# CAN-USB_adapter.net
KiCad netlist of a schematic drawn in EAGLE
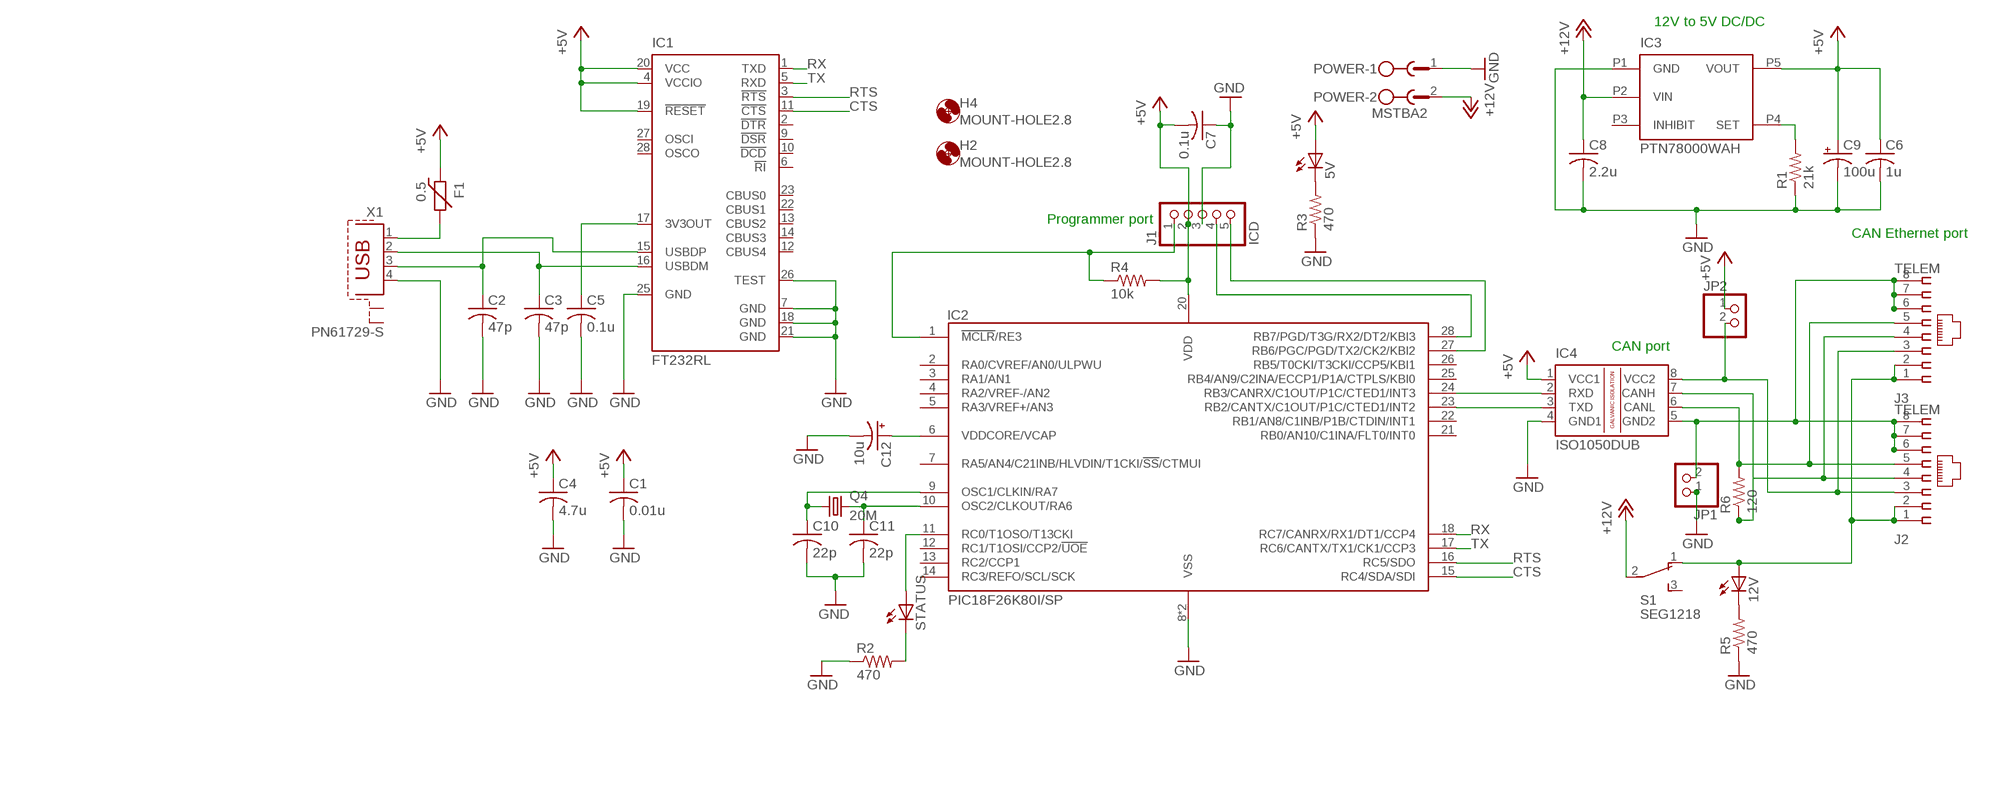
[diagram p0: schematic, sheet 1]

(export (version "E")
  (design (tool "Eeschema 10.0.6"))
  (components
    (comp (ref "5V")
      (value "LED5MM")
      (footprint "eagle-import:LED5MM")
      (libsource (lib "eagle-import") (part "LED5MM"))
    )
    (comp (ref "12V")
      (value "LED5MM")
      (footprint "eagle-import:LED5MM")
      (libsource (lib "eagle-import") (part "LED5MM"))
    )
    (comp (ref "C1")
      (value "0.01u")
      (footprint "eagle-import:C0805")
      (libsource (lib "eagle-import") (part "resistor_C-USC0805"))
    )
    (comp (ref "C2")
      (value "47p")
      (footprint "eagle-import:C0805")
      (libsource (lib "eagle-import") (part "resistor_C-USC0805"))
    )
    (comp (ref "C3")
      (value "47p")
      (footprint "eagle-import:C0805")
      (libsource (lib "eagle-import") (part "resistor_C-USC0805"))
    )
    (comp (ref "C4")
      (value "4.7u")
      (footprint "eagle-import:C0805")
      (libsource (lib "eagle-import") (part "resistor_C-USC0805"))
    )
    (comp (ref "C5")
      (value "0.1u")
      (footprint "eagle-import:C0805")
      (libsource (lib "eagle-import") (part "resistor_C-USC0805"))
    )
    (comp (ref "C6")
      (value "1u")
      (footprint "eagle-import:C0805")
      (libsource (lib "eagle-import") (part "C-USC0805"))
    )
    (comp (ref "C7")
      (value "0.1u")
      (footprint "eagle-import:C0805")
      (libsource (lib "eagle-import") (part "C-USC0805"))
    )
    (comp (ref "C8")
      (value "2.2u")
      (footprint "eagle-import:C1206")
      (libsource (lib "eagle-import") (part "C-USC1206"))
    )
    (comp (ref "C9")
      (value "100u")
      (footprint "eagle-import:SMC_D")
      (libsource (lib "eagle-import") (part "CPOL-USSMCD"))
    )
    (comp (ref "C10")
      (value "22p")
      (footprint "eagle-import:C0805")
      (libsource (lib "eagle-import") (part "C-USC0805"))
    )
    (comp (ref "C11")
      (value "22p")
      (footprint "eagle-import:C0805")
      (libsource (lib "eagle-import") (part "C-USC0805"))
    )
    (comp (ref "C12")
      (value "10u")
      (footprint "eagle-import:TT2D4")
      (libsource (lib "eagle-import") (part "CPOL-USTT2D4"))
    )
    (comp (ref "F1")
      (value "0.5")
      (footprint "eagle-import:F1206")
      (libsource (lib "eagle-import") (part "PTC0ZCA"))
    )
    (comp (ref "H2")
      (value "MOUNT-HOLE2.8")
      (footprint "eagle-import:2,8")
      (libsource (lib "eagle-import") (part "MOUNT-HOLE2.8"))
    )
    (comp (ref "H4")
      (value "MOUNT-HOLE2.8")
      (footprint "eagle-import:2,8")
      (libsource (lib "eagle-import") (part "MOUNT-HOLE2.8"))
    )
    (comp (ref "IC1")
      (value "FT232RL")
      (footprint "eagle-import:SSOP28")
      (libsource (lib "eagle-import") (part "FT232RL"))
    )
    (comp (ref "IC2")
      (value "PIC18F26K80I/SP")
      (footprint "eagle-import:DIL28_3")
      (libsource (lib "eagle-import") (part "PIC18F26K80I/SP"))
    )
    (comp (ref "IC3")
      (value "PTN78000WAH")
      (footprint "eagle-import:PTN78000")
      (libsource (lib "eagle-import") (part "PTN78000WAH"))
    )
    (comp (ref "IC4")
      (value "ISO1050DUB")
      (footprint "eagle-import:DUB-R-PDSO-G8")
      (fields (field (name "MPN") "ISO1050DUBR"))
      (libsource (lib "eagle-import") (part "ISO1050DUB"))
    )
    (comp (ref "J1")
      (value "ICD")
      (footprint "eagle-import:1X05")
      (libsource (lib "eagle-import") (part "PINHD-1X5"))
    )
    (comp (ref "J2")
      (value "TELEM")
      (footprint "eagle-import:215877-7")
      (libsource (lib "eagle-import") (part "215877-7"))
    )
    (comp (ref "J3")
      (value "TELEM")
      (footprint "eagle-import:215877-7")
      (libsource (lib "eagle-import") (part "215877-7"))
    )
    (comp (ref "JP1")
      (value "PINHD-1X2")
      (footprint "eagle-import:1X02")
      (libsource (lib "eagle-import") (part "PINHD-1X2"))
    )
    (comp (ref "JP2")
      (value "PINHD-1X2")
      (footprint "eagle-import:1X02")
      (libsource (lib "eagle-import") (part "PINHD-1X2"))
    )
    (comp (ref "POWER")
      (value "MSTBA2")
      (footprint "eagle-import:MSTBA2")
      (fields (field (name "MF") "FARNELL") (field (name "MPN") "1757242"))
      (libsource (lib "eagle-import") (part "MSTBA2"))
    )
    (comp (ref "Q4")
      (value "20M")
      (footprint "eagle-import:HC49_S")
      (libsource (lib "eagle-import") (part "CRYSTALHC49S"))
    )
    (comp (ref "R1")
      (value "21k")
      (footprint "eagle-import:R0805")
      (libsource (lib "eagle-import") (part "rcl_R-US_R0805"))
    )
    (comp (ref "R2")
      (value "470")
      (footprint "eagle-import:R0805")
      (libsource (lib "eagle-import") (part "rcl_R-US_R0805"))
    )
    (comp (ref "R3")
      (value "470")
      (footprint "eagle-import:R0805")
      (libsource (lib "eagle-import") (part "rcl_R-US_R0805"))
    )
    (comp (ref "R4")
      (value "10k")
      (footprint "eagle-import:R0805")
      (libsource (lib "eagle-import") (part "rcl_R-US_R0805"))
    )
    (comp (ref "R5")
      (value "470")
      (footprint "eagle-import:R0805")
      (libsource (lib "eagle-import") (part "rcl_R-US_R0805"))
    )
    (comp (ref "R6")
      (value "120")
      (footprint "eagle-import:0207_7")
      (libsource (lib "eagle-import") (part "R-US_0207/7"))
    )
    (comp (ref "S1")
      (value "SEG1218")
      (footprint "eagle-import:EG1218")
      (libsource (lib "eagle-import") (part "SEG1218"))
    )
    (comp (ref "STATUS")
      (value "LED5MM")
      (footprint "eagle-import:LED5MM")
      (libsource (lib "eagle-import") (part "LED5MM"))
    )
    (comp (ref "X1")
      (value "PN61729-S")
      (footprint "eagle-import:PN61729-S")
      (libsource (lib "eagle-import") (part "PN61729-S"))
    )
  )
  (nets
    (net (code "1") (name "+5V") (class "Default")
      (node (ref "5V") (pin "A") (pinfunction "A_A") (pintype "passive"))
      (node (ref "C1") (pin "1") (pinfunction "1_1") (pintype "passive"))
      (node (ref "C4") (pin "1") (pinfunction "1_1") (pintype "passive"))
      (node (ref "C6") (pin "1") (pinfunction "1_1") (pintype "passive"))
      (node (ref "C7") (pin "2") (pinfunction "2_2") (pintype "passive"))
      (node (ref "C9") (pin "+") (pinfunction "+_+") (pintype "passive"))
      (node (ref "F1") (pin "1") (pinfunction "1_1") (pintype "passive"))
      (node (ref "IC1") (pin "19") (pinfunction "~{RESET}_19") (pintype "input"))
      (node (ref "IC1") (pin "20") (pinfunction "VCC_20") (pintype "power_in"))
      (node (ref "IC1") (pin "4") (pinfunction "VCCIO_4") (pintype "power_in"))
      (node (ref "IC2") (pin "20") (pinfunction "VDD_20") (pintype "power_in"))
      (node (ref "IC3") (pin "P5") (pinfunction "VOUT_P5") (pintype "power_in"))
      (node (ref "IC4") (pin "1") (pinfunction "VCC1_1") (pintype "input"))
      (node (ref "J1") (pin "2") (pinfunction "2_2") (pintype "passive"))
      (node (ref "JP2") (pin "1") (pinfunction "1_1") (pintype "passive"))
      (node (ref "R4") (pin "2") (pinfunction "2_2") (pintype "passive"))
    )
    (net (code "2") (name "+12V") (class "Default")
      (node (ref "C8") (pin "1") (pinfunction "1_1") (pintype "passive"))
      (node (ref "IC3") (pin "P2") (pinfunction "VIN_P2") (pintype "power_in"))
      (node (ref "POWER") (pin "2") (pinfunction "1_2") (pintype "passive"))
      (node (ref "S1") (pin "2") (pinfunction "P_2") (pintype "passive"))
    )
    (net (code "3") (name "/CTS") (class "Default")
      (node (ref "IC1") (pin "11") (pinfunction "~{CTS}_11") (pintype "bidirectional"))
      (node (ref "IC2") (pin "15") (pinfunction "RC4/SDA/SDI_15") (pintype "bidirectional"))
    )
    (net (code "4") (name "/RTS") (class "Default")
      (node (ref "IC1") (pin "3") (pinfunction "~{RTS}_3") (pintype "bidirectional"))
      (node (ref "IC2") (pin "16") (pinfunction "RC5/SDO_16") (pintype "bidirectional"))
    )
    (net (code "5") (name "/RX") (class "Default")
      (node (ref "IC1") (pin "1") (pinfunction "TXD_1") (pintype "output"))
      (node (ref "IC2") (pin "18") (pinfunction "RC7/CANRX/RX1/DT1/CCP4_18") (pintype "bidirectional"))
    )
    (net (code "6") (name "/TX") (class "Default")
      (node (ref "IC1") (pin "5") (pinfunction "RXD_5") (pintype "input"))
      (node (ref "IC2") (pin "17") (pinfunction "RC6/CANTX/TX1/CK1/CCP3_17") (pintype "bidirectional"))
    )
    (net (code "7") (name "GND") (class "Default")
      (node (ref "C1") (pin "2") (pinfunction "2_2") (pintype "passive"))
      (node (ref "C10") (pin "2") (pinfunction "2_2") (pintype "passive"))
      (node (ref "C11") (pin "2") (pinfunction "2_2") (pintype "passive"))
      (node (ref "C12") (pin "-") (pinfunction "-_-") (pintype "passive"))
      (node (ref "C2") (pin "2") (pinfunction "2_2") (pintype "passive"))
      (node (ref "C3") (pin "2") (pinfunction "2_2") (pintype "passive"))
      (node (ref "C4") (pin "2") (pinfunction "2_2") (pintype "passive"))
      (node (ref "C5") (pin "2") (pinfunction "2_2") (pintype "passive"))
      (node (ref "C6") (pin "2") (pinfunction "2_2") (pintype "passive"))
      (node (ref "C7") (pin "1") (pinfunction "1_1") (pintype "passive"))
      (node (ref "C8") (pin "2") (pinfunction "2_2") (pintype "passive"))
      (node (ref "C9") (pin "-") (pinfunction "-_-") (pintype "passive"))
      (node (ref "IC1") (pin "18") (pinfunction "GND_18") (pintype "power_in"))
      (node (ref "IC1") (pin "21") (pinfunction "GND_21") (pintype "power_in"))
      (node (ref "IC1") (pin "25") (pinfunction "GND_25") (pintype "power_in"))
      (node (ref "IC1") (pin "26") (pinfunction "TEST_26") (pintype "input"))
      (node (ref "IC1") (pin "7") (pinfunction "GND_7") (pintype "power_in"))
      (node (ref "IC2") (pin "19") (pinfunction "VSS_19") (pintype "power_in"))
      (node (ref "IC2") (pin "8") (pinfunction "VSS_8") (pintype "power_in"))
      (node (ref "IC3") (pin "P1") (pinfunction "GND_P1") (pintype "power_in"))
      (node (ref "IC4") (pin "4") (pinfunction "GND1_4") (pintype "input"))
      (node (ref "J1") (pin "3") (pinfunction "3_3") (pintype "passive"))
      (node (ref "JP1") (pin "1") (pinfunction "1_1") (pintype "passive"))
      (node (ref "POWER") (pin "1") (pinfunction "1_1") (pintype "passive"))
      (node (ref "R1") (pin "1") (pinfunction "1_1") (pintype "passive"))
      (node (ref "R2") (pin "1") (pinfunction "1_1") (pintype "passive"))
      (node (ref "R3") (pin "1") (pinfunction "1_1") (pintype "passive"))
      (node (ref "R5") (pin "1") (pinfunction "1_1") (pintype "passive"))
      (node (ref "X1") (pin "4") (pinfunction "4_4") (pintype "passive"))
    )
    (net (code "8") (name "Net-(5V-C)") (class "Default")
      (node (ref "5V") (pin "K") (pinfunction "C_K") (pintype "passive"))
      (node (ref "R3") (pin "2") (pinfunction "2_2") (pintype "passive"))
    )
    (net (code "9") (name "Net-(12V-C)") (class "Default")
      (node (ref "12V") (pin "K") (pinfunction "C_K") (pintype "passive"))
      (node (ref "R5") (pin "2") (pinfunction "2_2") (pintype "passive"))
    )
    (net (code "10") (name "Net-(F1-Pad2)") (class "Default")
      (node (ref "F1") (pin "2") (pinfunction "2_2") (pintype "passive"))
      (node (ref "X1") (pin "1") (pinfunction "1_1") (pintype "passive"))
    )
    (net (code "11") (name "Net-(IC1-3V3OUT)") (class "Default")
      (node (ref "C5") (pin "1") (pinfunction "1_1") (pintype "passive"))
      (node (ref "IC1") (pin "17") (pinfunction "3V3OUT_17") (pintype "output"))
    )
    (net (code "12") (name "Net-(IC1-USBDM)") (class "Default")
      (node (ref "C3") (pin "1") (pinfunction "1_1") (pintype "passive"))
      (node (ref "IC1") (pin "16") (pinfunction "USBDM_16") (pintype "bidirectional"))
      (node (ref "X1") (pin "2") (pinfunction "2_2") (pintype "passive"))
    )
    (net (code "13") (name "Net-(IC1-USBDP)") (class "Default")
      (node (ref "C2") (pin "1") (pinfunction "1_1") (pintype "passive"))
      (node (ref "IC1") (pin "15") (pinfunction "USBDP_15") (pintype "bidirectional"))
      (node (ref "X1") (pin "3") (pinfunction "3_3") (pintype "passive"))
    )
    (net (code "14") (name "Net-(IC2-OSC1{slash}CLKIN{slash}RA7)") (class "Default")
      (node (ref "C10") (pin "1") (pinfunction "1_1") (pintype "passive"))
      (node (ref "IC2") (pin "9") (pinfunction "OSC1/CLKIN/RA7_9") (pintype "bidirectional"))
      (node (ref "Q4") (pin "1") (pinfunction "1_1") (pintype "passive"))
    )
    (net (code "15") (name "Net-(IC2-OSC2{slash}CLKOUT{slash}RA6)") (class "Default")
      (node (ref "C11") (pin "1") (pinfunction "1_1") (pintype "passive"))
      (node (ref "IC2") (pin "10") (pinfunction "OSC2/CLKOUT/RA6_10") (pintype "bidirectional"))
      (node (ref "Q4") (pin "2") (pinfunction "2_2") (pintype "passive"))
    )
    (net (code "16") (name "Net-(IC2-RB2{slash}CANTX{slash}C1OUT{slash}P1C{slash}CTED1{slash}INT2)") (class "Default")
      (node (ref "IC2") (pin "23") (pinfunction "RB2/CANTX/C1OUT/P1C/CTED1/INT2_23") (pintype "bidirectional"))
      (node (ref "IC4") (pin "3") (pinfunction "TXD_3") (pintype "input"))
    )
    (net (code "17") (name "Net-(IC2-RB3{slash}CANRX{slash}C1OUT{slash}P1C{slash}CTED1{slash}INT3)") (class "Default")
      (node (ref "IC2") (pin "24") (pinfunction "RB3/CANRX/C1OUT/P1C/CTED1/INT3_24") (pintype "bidirectional"))
      (node (ref "IC4") (pin "2") (pinfunction "RXD_2") (pintype "input"))
    )
    (net (code "18") (name "Net-(IC2-RB6{slash}PGC{slash}PGD{slash}TX2{slash}CK2{slash}KBI2)") (class "Default")
      (node (ref "IC2") (pin "27") (pinfunction "RB6/PGC/PGD/TX2/CK2/KBI2_27") (pintype "bidirectional"))
      (node (ref "J1") (pin "5") (pinfunction "5_5") (pintype "passive"))
    )
    (net (code "19") (name "Net-(IC2-RB7{slash}PGD{slash}T3G{slash}RX2{slash}DT2{slash}KBI3)") (class "Default")
      (node (ref "IC2") (pin "28") (pinfunction "RB7/PGD/T3G/RX2/DT2/KBI3_28") (pintype "bidirectional"))
      (node (ref "J1") (pin "4") (pinfunction "4_4") (pintype "passive"))
    )
    (net (code "20") (name "Net-(IC2-RC0{slash}T1OSO{slash}T13CKI)") (class "Default")
      (node (ref "IC2") (pin "11") (pinfunction "RC0/T1OSO/T13CKI_11") (pintype "bidirectional"))
      (node (ref "STATUS") (pin "A") (pinfunction "A_A") (pintype "passive"))
    )
    (net (code "21") (name "Net-(IC2-VDDCORE{slash}VCAP)") (class "Default")
      (node (ref "C12") (pin "+") (pinfunction "+_+") (pintype "passive"))
      (node (ref "IC2") (pin "6") (pinfunction "VDDCORE/VCAP_6") (pintype "bidirectional"))
    )
    (net (code "22") (name "Net-(IC2-~{MCLR}{slash}RE3)") (class "Default")
      (node (ref "IC2") (pin "1") (pinfunction "~{MCLR}/RE3_1") (pintype "input"))
      (node (ref "J1") (pin "1") (pinfunction "1_1") (pintype "passive"))
      (node (ref "R4") (pin "1") (pinfunction "1_1") (pintype "passive"))
    )
    (net (code "23") (name "Net-(IC3-SET)") (class "Default")
      (node (ref "IC3") (pin "P4") (pinfunction "SET_P4") (pintype "bidirectional"))
      (node (ref "R1") (pin "2") (pinfunction "2_2") (pintype "passive"))
    )
    (net (code "24") (name "Net-(IC4-CANH)") (class "Default")
      (node (ref "IC4") (pin "7") (pinfunction "CANH_7") (pintype "input"))
      (node (ref "J2") (pin "4") (pinfunction "4_4") (pintype "passive"))
      (node (ref "J3") (pin "4") (pinfunction "4_4") (pintype "passive"))
      (node (ref "R6") (pin "1") (pinfunction "1_1") (pintype "passive"))
    )
    (net (code "25") (name "Net-(IC4-CANL)") (class "Default")
      (node (ref "IC4") (pin "6") (pinfunction "CANL_6") (pintype "input"))
      (node (ref "J2") (pin "5") (pinfunction "5_5") (pintype "passive"))
      (node (ref "J3") (pin "5") (pinfunction "5_5") (pintype "passive"))
      (node (ref "R6") (pin "2") (pinfunction "2_2") (pintype "passive"))
    )
    (net (code "26") (name "Net-(IC4-GND2)") (class "Default")
      (node (ref "IC4") (pin "5") (pinfunction "GND2_5") (pintype "input"))
      (node (ref "J2") (pin "6") (pinfunction "6_6") (pintype "passive"))
      (node (ref "J2") (pin "7") (pinfunction "7_7") (pintype "passive"))
      (node (ref "J2") (pin "8") (pinfunction "8_8") (pintype "passive"))
      (node (ref "J3") (pin "6") (pinfunction "6_6") (pintype "passive"))
      (node (ref "J3") (pin "7") (pinfunction "7_7") (pintype "passive"))
      (node (ref "J3") (pin "8") (pinfunction "8_8") (pintype "passive"))
      (node (ref "JP1") (pin "2") (pinfunction "2_2") (pintype "passive"))
    )
    (net (code "27") (name "Net-(IC4-VCC2)") (class "Default")
      (node (ref "IC4") (pin "8") (pinfunction "VCC2_8") (pintype "input"))
      (node (ref "J2") (pin "3") (pinfunction "3_3") (pintype "passive"))
      (node (ref "J3") (pin "3") (pinfunction "3_3") (pintype "passive"))
      (node (ref "JP2") (pin "2") (pinfunction "2_2") (pintype "passive"))
    )
    (net (code "28") (name "Net-(S1-O)") (class "Default")
      (node (ref "12V") (pin "A") (pinfunction "A_A") (pintype "passive"))
      (node (ref "J2") (pin "1") (pinfunction "1_1") (pintype "passive"))
      (node (ref "J2") (pin "2") (pinfunction "2_2") (pintype "passive"))
      (node (ref "J3") (pin "1") (pinfunction "1_1") (pintype "passive"))
      (node (ref "J3") (pin "2") (pinfunction "2_2") (pintype "passive"))
      (node (ref "S1") (pin "1") (pinfunction "O_1") (pintype "passive"))
    )
    (net (code "29") (name "Net-(STATUS-C)") (class "Default")
      (node (ref "R2") (pin "2") (pinfunction "2_2") (pintype "passive"))
      (node (ref "STATUS") (pin "K") (pinfunction "C_K") (pintype "passive"))
    )
    (net (code "30") (name "unconnected-(IC1-CBUS0-Pad23)") (class "Default")
      (node (ref "IC1") (pin "23") (pinfunction "CBUS0_23") (pintype "bidirectional"))
    )
    (net (code "31") (name "unconnected-(IC1-CBUS1-Pad22)") (class "Default")
      (node (ref "IC1") (pin "22") (pinfunction "CBUS1_22") (pintype "bidirectional"))
    )
    (net (code "32") (name "unconnected-(IC1-CBUS2-Pad13)") (class "Default")
      (node (ref "IC1") (pin "13") (pinfunction "CBUS2_13") (pintype "bidirectional"))
    )
    (net (code "33") (name "unconnected-(IC1-CBUS3-Pad14)") (class "Default")
      (node (ref "IC1") (pin "14") (pinfunction "CBUS3_14") (pintype "bidirectional"))
    )
    (net (code "34") (name "unconnected-(IC1-CBUS4-Pad12)") (class "Default")
      (node (ref "IC1") (pin "12") (pinfunction "CBUS4_12") (pintype "bidirectional"))
    )
    (net (code "35") (name "unconnected-(IC1-OSCI-Pad27)") (class "Default")
      (node (ref "IC1") (pin "27") (pinfunction "OSCI_27") (pintype "bidirectional"))
    )
    (net (code "36") (name "unconnected-(IC1-OSCO-Pad28)") (class "Default")
      (node (ref "IC1") (pin "28") (pinfunction "OSCO_28") (pintype "output"))
    )
    (net (code "37") (name "unconnected-(IC1-~{DCD}-Pad10)") (class "Default")
      (node (ref "IC1") (pin "10") (pinfunction "~{DCD}_10") (pintype "bidirectional"))
    )
    (net (code "38") (name "unconnected-(IC1-~{DSR}-Pad9)") (class "Default")
      (node (ref "IC1") (pin "9") (pinfunction "~{DSR}_9") (pintype "bidirectional"))
    )
    (net (code "39") (name "unconnected-(IC1-~{DTR}-Pad2)") (class "Default")
      (node (ref "IC1") (pin "2") (pinfunction "~{DTR}_2") (pintype "bidirectional"))
    )
    (net (code "40") (name "unconnected-(IC1-~{RI}-Pad6)") (class "Default")
      (node (ref "IC1") (pin "6") (pinfunction "~{RI}_6") (pintype "bidirectional"))
    )
    (net (code "41") (name "unconnected-(IC2-RA0{slash}CVREF{slash}AN0{slash}ULPWU-Pad2)") (class "Default")
      (node (ref "IC2") (pin "2") (pinfunction "RA0/CVREF/AN0/ULPWU_2") (pintype "bidirectional"))
    )
    (net (code "42") (name "unconnected-(IC2-RA1{slash}AN1-Pad3)") (class "Default")
      (node (ref "IC2") (pin "3") (pinfunction "RA1/AN1_3") (pintype "bidirectional"))
    )
    (net (code "43") (name "unconnected-(IC2-RA2{slash}VREF-{slash}AN2-Pad4)") (class "Default")
      (node (ref "IC2") (pin "4") (pinfunction "RA2/VREF-/AN2_4") (pintype "bidirectional"))
    )
    (net (code "44") (name "unconnected-(IC2-RA3{slash}VREF+{slash}AN3-Pad5)") (class "Default")
      (node (ref "IC2") (pin "5") (pinfunction "RA3/VREF+/AN3_5") (pintype "bidirectional"))
    )
    (net (code "45") (name "unconnected-(IC2-RA5{slash}AN4{slash}C21INB{slash}HLVDIN{slash}T1CKI{slash}~{SS}{slash}CTMUI-Pad7)") (class "Default")
      (node (ref "IC2") (pin "7") (pinfunction "RA5/AN4/C21INB/HLVDIN/T1CKI/~{SS}/CTMUI_7") (pintype "bidirectional"))
    )
    (net (code "46") (name "unconnected-(IC2-RB0{slash}AN10{slash}C1INA{slash}FLT0{slash}INT0-Pad21)") (class "Default")
      (node (ref "IC2") (pin "21") (pinfunction "RB0/AN10/C1INA/FLT0/INT0_21") (pintype "bidirectional"))
    )
    (net (code "47") (name "unconnected-(IC2-RB1{slash}AN8{slash}C1INB{slash}P1B{slash}CTDIN{slash}INT1-Pad22)") (class "Default")
      (node (ref "IC2") (pin "22") (pinfunction "RB1/AN8/C1INB/P1B/CTDIN/INT1_22") (pintype "bidirectional"))
    )
    (net (code "48") (name "unconnected-(IC2-RB4{slash}AN9{slash}C2INA{slash}ECCP1{slash}P1A{slash}CTPLS{slash}KBI0-Pad25)") (class "Default")
      (node (ref "IC2") (pin "25") (pinfunction "RB4/AN9/C2INA/ECCP1/P1A/CTPLS/KBI0_25") (pintype "bidirectional"))
    )
    (net (code "49") (name "unconnected-(IC2-RB5{slash}T0CKI{slash}T3CKI{slash}CCP5{slash}KBI1-Pad26)") (class "Default")
      (node (ref "IC2") (pin "26") (pinfunction "RB5/T0CKI/T3CKI/CCP5/KBI1_26") (pintype "bidirectional"))
    )
    (net (code "50") (name "unconnected-(IC2-RC1{slash}T1OSI{slash}CCP2{slash}~{UOE}-Pad12)") (class "Default")
      (node (ref "IC2") (pin "12") (pinfunction "RC1/T1OSI/CCP2/~{UOE}_12") (pintype "bidirectional"))
    )
    (net (code "51") (name "unconnected-(IC2-RC2{slash}CCP1-Pad13)") (class "Default")
      (node (ref "IC2") (pin "13") (pinfunction "RC2/CCP1_13") (pintype "bidirectional"))
    )
    (net (code "52") (name "unconnected-(IC2-RC3{slash}REFO{slash}SCL{slash}SCK-Pad14)") (class "Default")
      (node (ref "IC2") (pin "14") (pinfunction "RC3/REFO/SCL/SCK_14") (pintype "bidirectional"))
    )
    (net (code "53") (name "unconnected-(IC3-INHIBIT-PadP3)") (class "Default")
      (node (ref "IC3") (pin "P3") (pinfunction "INHIBIT_P3") (pintype "bidirectional"))
    )
    (net (code "54") (name "unconnected-(S1-S-Pad3)") (class "Default")
      (node (ref "S1") (pin "3") (pinfunction "S_3") (pintype "passive"))
    )
    (net (code "55") (name "unconnected-(X1-PadS1)") (class "Default")
      (node (ref "X1") (pin "S1") (pinfunction "S1_S1") (pintype "passive"))
    )
    (net (code "56") (name "unconnected-(X1-PadS2)") (class "Default")
      (node (ref "X1") (pin "S2") (pinfunction "S2_S2") (pintype "passive"))
    )
  )
)
